# PCBFAB.net
KiCad netlist of a schematic drawn in EAGLE
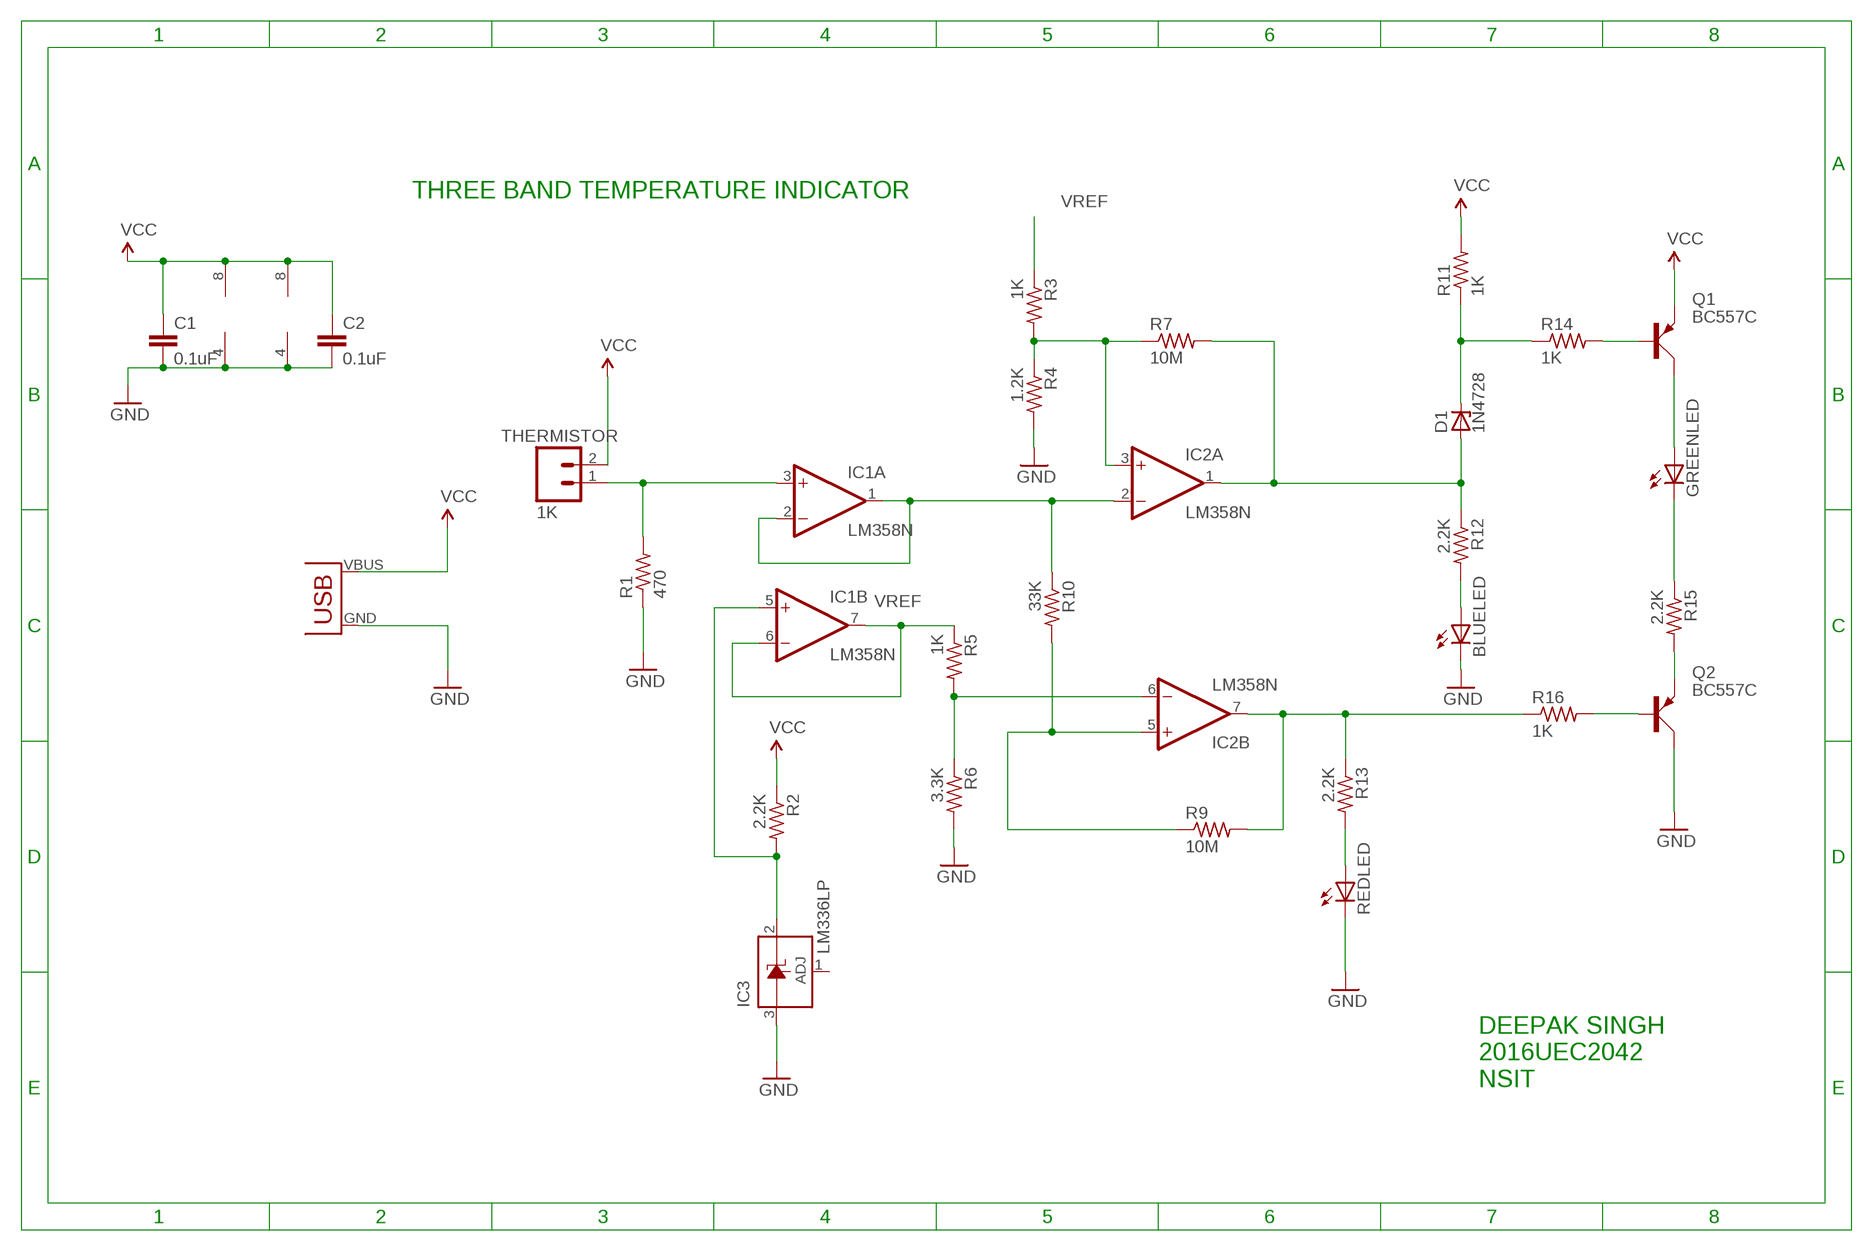
[diagram p0: schematic, sheet 1]

(export (version "E")
  (design (tool "Eeschema 10.0.6"))
  (components
    (comp (ref "BLUELED")
      (value "LED5MM")
      (footprint "eagle-import:LED5MM")
      (libsource (lib "eagle-import") (part "LED5MM"))
    )
    (comp (ref "C1")
      (value "0.1uF")
      (footprint "eagle-import:C025-024X044")
      (libsource (lib "eagle-import") (part "C-EU025-024X044"))
    )
    (comp (ref "C2")
      (value "0.1uF")
      (footprint "eagle-import:C025-024X044")
      (libsource (lib "eagle-import") (part "C-EU025-024X044"))
    )
    (comp (ref "D1")
      (value "1N4728")
      (footprint "eagle-import:DO41Z10")
      (libsource (lib "eagle-import") (part "1N4728"))
    )
    (comp (ref "GREENLED")
      (value "LED5MM")
      (footprint "eagle-import:LED5MM")
      (libsource (lib "eagle-import") (part "LED5MM"))
    )
    (comp (ref "IC1")
      (value "LM358N")
      (footprint "eagle-import:DIL08")
      (libsource (lib "eagle-import") (part "LM358N"))
    )
    (comp (ref "IC2")
      (value "LM358N")
      (footprint "eagle-import:DIL08")
      (libsource (lib "eagle-import") (part "LM358N"))
    )
    (comp (ref "IC3")
      (value "LM336LP")
      (footprint "eagle-import:TO92")
      (libsource (lib "eagle-import") (part "LM336LP"))
    )
    (comp (ref "Q1")
      (value "BC557C")
      (footprint "eagle-import:SOT54A")
      (libsource (lib "eagle-import") (part "BC557"))
    )
    (comp (ref "Q2")
      (value "BC557C")
      (footprint "eagle-import:SOT54A")
      (libsource (lib "eagle-import") (part "BC557"))
    )
    (comp (ref "R1")
      (value "470")
      (footprint "eagle-import:0204_7")
      (libsource (lib "eagle-import") (part "R-US_0204/7"))
    )
    (comp (ref "R2")
      (value "2.2K")
      (footprint "eagle-import:0204_7")
      (libsource (lib "eagle-import") (part "R-US_0204/7"))
    )
    (comp (ref "R3")
      (value "1K")
      (footprint "eagle-import:0204_7")
      (libsource (lib "eagle-import") (part "R-US_0204/7"))
    )
    (comp (ref "R4")
      (value "1.2K")
      (footprint "eagle-import:0204_7")
      (libsource (lib "eagle-import") (part "R-US_0204/7"))
    )
    (comp (ref "R5")
      (value "1K")
      (footprint "eagle-import:0204_7")
      (libsource (lib "eagle-import") (part "R-US_0204/7"))
    )
    (comp (ref "R6")
      (value "3.3K")
      (footprint "eagle-import:0204_7")
      (libsource (lib "eagle-import") (part "R-US_0204/7"))
    )
    (comp (ref "R7")
      (value "10M")
      (footprint "eagle-import:0204_7")
      (libsource (lib "eagle-import") (part "R-US_0204/7"))
    )
    (comp (ref "R9")
      (value "10M")
      (footprint "eagle-import:0204_7")
      (libsource (lib "eagle-import") (part "R-US_0204/7"))
    )
    (comp (ref "R10")
      (value "33K")
      (footprint "eagle-import:0204_7")
      (libsource (lib "eagle-import") (part "R-US_0204/7"))
    )
    (comp (ref "R11")
      (value "1K")
      (footprint "eagle-import:0204_7")
      (libsource (lib "eagle-import") (part "R-US_0204/7"))
    )
    (comp (ref "R12")
      (value "2.2K")
      (footprint "eagle-import:0204_7")
      (libsource (lib "eagle-import") (part "R-US_0204/7"))
    )
    (comp (ref "R13")
      (value "2.2K")
      (footprint "eagle-import:0204_7")
      (libsource (lib "eagle-import") (part "R-US_0204/7"))
    )
    (comp (ref "R14")
      (value "1K")
      (footprint "eagle-import:0204_7")
      (libsource (lib "eagle-import") (part "R-US_0204/7"))
    )
    (comp (ref "R15")
      (value "2.2K")
      (footprint "eagle-import:0204_7")
      (libsource (lib "eagle-import") (part "R-US_0204/7"))
    )
    (comp (ref "R16")
      (value "1K")
      (footprint "eagle-import:0204_7")
      (libsource (lib "eagle-import") (part "R-US_0204/7"))
    )
    (comp (ref "REDLED")
      (value "LED5MM")
      (footprint "eagle-import:LED5MM")
      (libsource (lib "eagle-import") (part "LED5MM"))
    )
    (comp (ref "THERMISTOR")
      (value "1K")
      (footprint "eagle-import:02P")
      (libsource (lib "eagle-import") (part "M02"))
    )
    (comp (ref "U$1")
      (value "USB(POWER)")
      (footprint "eagle-import:USB(POWER)")
      (libsource (lib "eagle-import") (part "USB(POWER)"))
    )
  )
  (nets
    (net (code "1") (name "/VREF") (class "Default")
      (node (ref "IC1") (pin "6") (pinfunction "-IN_6") (pintype "input"))
      (node (ref "IC1") (pin "7") (pinfunction "OUT_7") (pintype "output"))
      (node (ref "R3") (pin "1") (pinfunction "1_1") (pintype "passive"))
      (node (ref "R5") (pin "1") (pinfunction "1_1") (pintype "passive"))
    )
    (net (code "2") (name "GND") (class "Default")
      (node (ref "BLUELED") (pin "K") (pinfunction "C_K") (pintype "passive"))
      (node (ref "C1") (pin "2") (pinfunction "2_2") (pintype "passive"))
      (node (ref "C2") (pin "2") (pinfunction "2_2") (pintype "passive"))
      (node (ref "IC1") (pin "4") (pinfunction "V-_4") (pintype "power_in"))
      (node (ref "IC2") (pin "4") (pinfunction "V-_4") (pintype "power_in"))
      (node (ref "IC3") (pin "3") (pinfunction "A_3") (pintype "input"))
      (node (ref "Q2") (pin "C") (pinfunction "C_C") (pintype "passive"))
      (node (ref "R1") (pin "1") (pinfunction "1_1") (pintype "passive"))
      (node (ref "R4") (pin "2") (pinfunction "2_2") (pintype "passive"))
      (node (ref "R6") (pin "2") (pinfunction "2_2") (pintype "passive"))
      (node (ref "REDLED") (pin "K") (pinfunction "C_K") (pintype "passive"))
      (node (ref "U$1") (pin "GND") (pinfunction "GND_GND") (pintype "power_in"))
    )
    (net (code "3") (name "Net-(BLUELED-PadA)") (class "Default")
      (node (ref "BLUELED") (pin "A") (pinfunction "A_A") (pintype "passive"))
      (node (ref "R12") (pin "2") (pinfunction "2_2") (pintype "passive"))
    )
    (net (code "4") (name "Net-(D1-PadC)") (class "Default")
      (node (ref "D1") (pin "C") (pinfunction "C_C") (pintype "passive"))
      (node (ref "R11") (pin "1") (pinfunction "1_1") (pintype "passive"))
      (node (ref "R14") (pin "1") (pinfunction "1_1") (pintype "passive"))
    )
    (net (code "5") (name "Net-(GREENLED-C)") (class "Default")
      (node (ref "GREENLED") (pin "K") (pinfunction "C_K") (pintype "passive"))
      (node (ref "R15") (pin "1") (pinfunction "1_1") (pintype "passive"))
    )
    (net (code "6") (name "Net-(GREENLED-PadA)") (class "Default")
      (node (ref "GREENLED") (pin "A") (pinfunction "A_A") (pintype "passive"))
      (node (ref "Q1") (pin "C") (pinfunction "C_C") (pintype "passive"))
    )
    (net (code "7") (name "Net-(IC1A-+IN)") (class "Default")
      (node (ref "IC1") (pin "3") (pinfunction "+IN_3") (pintype "input"))
      (node (ref "R1") (pin "2") (pinfunction "2_2") (pintype "passive"))
      (node (ref "THERMISTOR") (pin "1") (pinfunction "1_1") (pintype "passive"))
    )
    (net (code "8") (name "Net-(IC1A--IN)") (class "Default")
      (node (ref "IC1") (pin "1") (pinfunction "OUT_1") (pintype "output"))
      (node (ref "IC1") (pin "2") (pinfunction "-IN_2") (pintype "input"))
      (node (ref "IC2") (pin "2") (pinfunction "-IN_2") (pintype "input"))
      (node (ref "R10") (pin "1") (pinfunction "1_1") (pintype "passive"))
    )
    (net (code "9") (name "Net-(IC1B-+IN)") (class "Default")
      (node (ref "IC1") (pin "5") (pinfunction "+IN_5") (pintype "input"))
      (node (ref "IC3") (pin "2") (pinfunction "C_2") (pintype "passive"))
      (node (ref "R2") (pin "2") (pinfunction "2_2") (pintype "passive"))
    )
    (net (code "10") (name "Net-(IC2A-+IN)") (class "Default")
      (node (ref "IC2") (pin "3") (pinfunction "+IN_3") (pintype "input"))
      (node (ref "R3") (pin "2") (pinfunction "2_2") (pintype "passive"))
      (node (ref "R4") (pin "1") (pinfunction "1_1") (pintype "passive"))
      (node (ref "R7") (pin "1") (pinfunction "1_1") (pintype "passive"))
    )
    (net (code "11") (name "Net-(IC2A-OUT)") (class "Default")
      (node (ref "D1") (pin "A") (pinfunction "A_A") (pintype "passive"))
      (node (ref "IC2") (pin "1") (pinfunction "OUT_1") (pintype "output"))
      (node (ref "R12") (pin "1") (pinfunction "1_1") (pintype "passive"))
      (node (ref "R7") (pin "2") (pinfunction "2_2") (pintype "passive"))
    )
    (net (code "12") (name "Net-(IC2B-+IN)") (class "Default")
      (node (ref "IC2") (pin "5") (pinfunction "+IN_5") (pintype "input"))
      (node (ref "R10") (pin "2") (pinfunction "2_2") (pintype "passive"))
      (node (ref "R9") (pin "1") (pinfunction "1_1") (pintype "passive"))
    )
    (net (code "13") (name "Net-(IC2B--IN)") (class "Default")
      (node (ref "IC2") (pin "6") (pinfunction "-IN_6") (pintype "input"))
      (node (ref "R5") (pin "2") (pinfunction "2_2") (pintype "passive"))
      (node (ref "R6") (pin "1") (pinfunction "1_1") (pintype "passive"))
    )
    (net (code "14") (name "Net-(IC2B-OUT)") (class "Default")
      (node (ref "IC2") (pin "7") (pinfunction "OUT_7") (pintype "output"))
      (node (ref "R13") (pin "1") (pinfunction "1_1") (pintype "passive"))
      (node (ref "R16") (pin "1") (pinfunction "1_1") (pintype "passive"))
      (node (ref "R9") (pin "2") (pinfunction "2_2") (pintype "passive"))
    )
    (net (code "15") (name "Net-(Q1-PadB)") (class "Default")
      (node (ref "Q1") (pin "B") (pinfunction "B_B") (pintype "passive"))
      (node (ref "R14") (pin "2") (pinfunction "2_2") (pintype "passive"))
    )
    (net (code "16") (name "Net-(Q2-PadB)") (class "Default")
      (node (ref "Q2") (pin "B") (pinfunction "B_B") (pintype "passive"))
      (node (ref "R16") (pin "2") (pinfunction "2_2") (pintype "passive"))
    )
    (net (code "17") (name "Net-(Q2-PadE)") (class "Default")
      (node (ref "Q2") (pin "E") (pinfunction "E_E") (pintype "passive"))
      (node (ref "R15") (pin "2") (pinfunction "2_2") (pintype "passive"))
    )
    (net (code "18") (name "Net-(R13-Pad2)") (class "Default")
      (node (ref "R13") (pin "2") (pinfunction "2_2") (pintype "passive"))
      (node (ref "REDLED") (pin "A") (pinfunction "A_A") (pintype "passive"))
    )
    (net (code "19") (name "VCC") (class "Default")
      (node (ref "C1") (pin "1") (pinfunction "1_1") (pintype "passive"))
      (node (ref "C2") (pin "1") (pinfunction "1_1") (pintype "passive"))
      (node (ref "IC1") (pin "8") (pinfunction "V+_8") (pintype "power_in"))
      (node (ref "IC2") (pin "8") (pinfunction "V+_8") (pintype "power_in"))
      (node (ref "Q1") (pin "E") (pinfunction "E_E") (pintype "passive"))
      (node (ref "R11") (pin "2") (pinfunction "2_2") (pintype "passive"))
      (node (ref "R2") (pin "1") (pinfunction "1_1") (pintype "passive"))
      (node (ref "THERMISTOR") (pin "2") (pinfunction "2_2") (pintype "passive"))
      (node (ref "U$1") (pin "VBUS") (pinfunction "VCC_VBUS") (pintype "power_in"))
    )
    (net (code "20") (name "unconnected-(IC3-ADJ-Pad1)") (class "Default")
      (node (ref "IC3") (pin "1") (pinfunction "ADJ_1") (pintype "input"))
    )
  )
)
